# P07_DDR3_Memory.net
KiCad netlist of a schematic drawn in Altium Designer
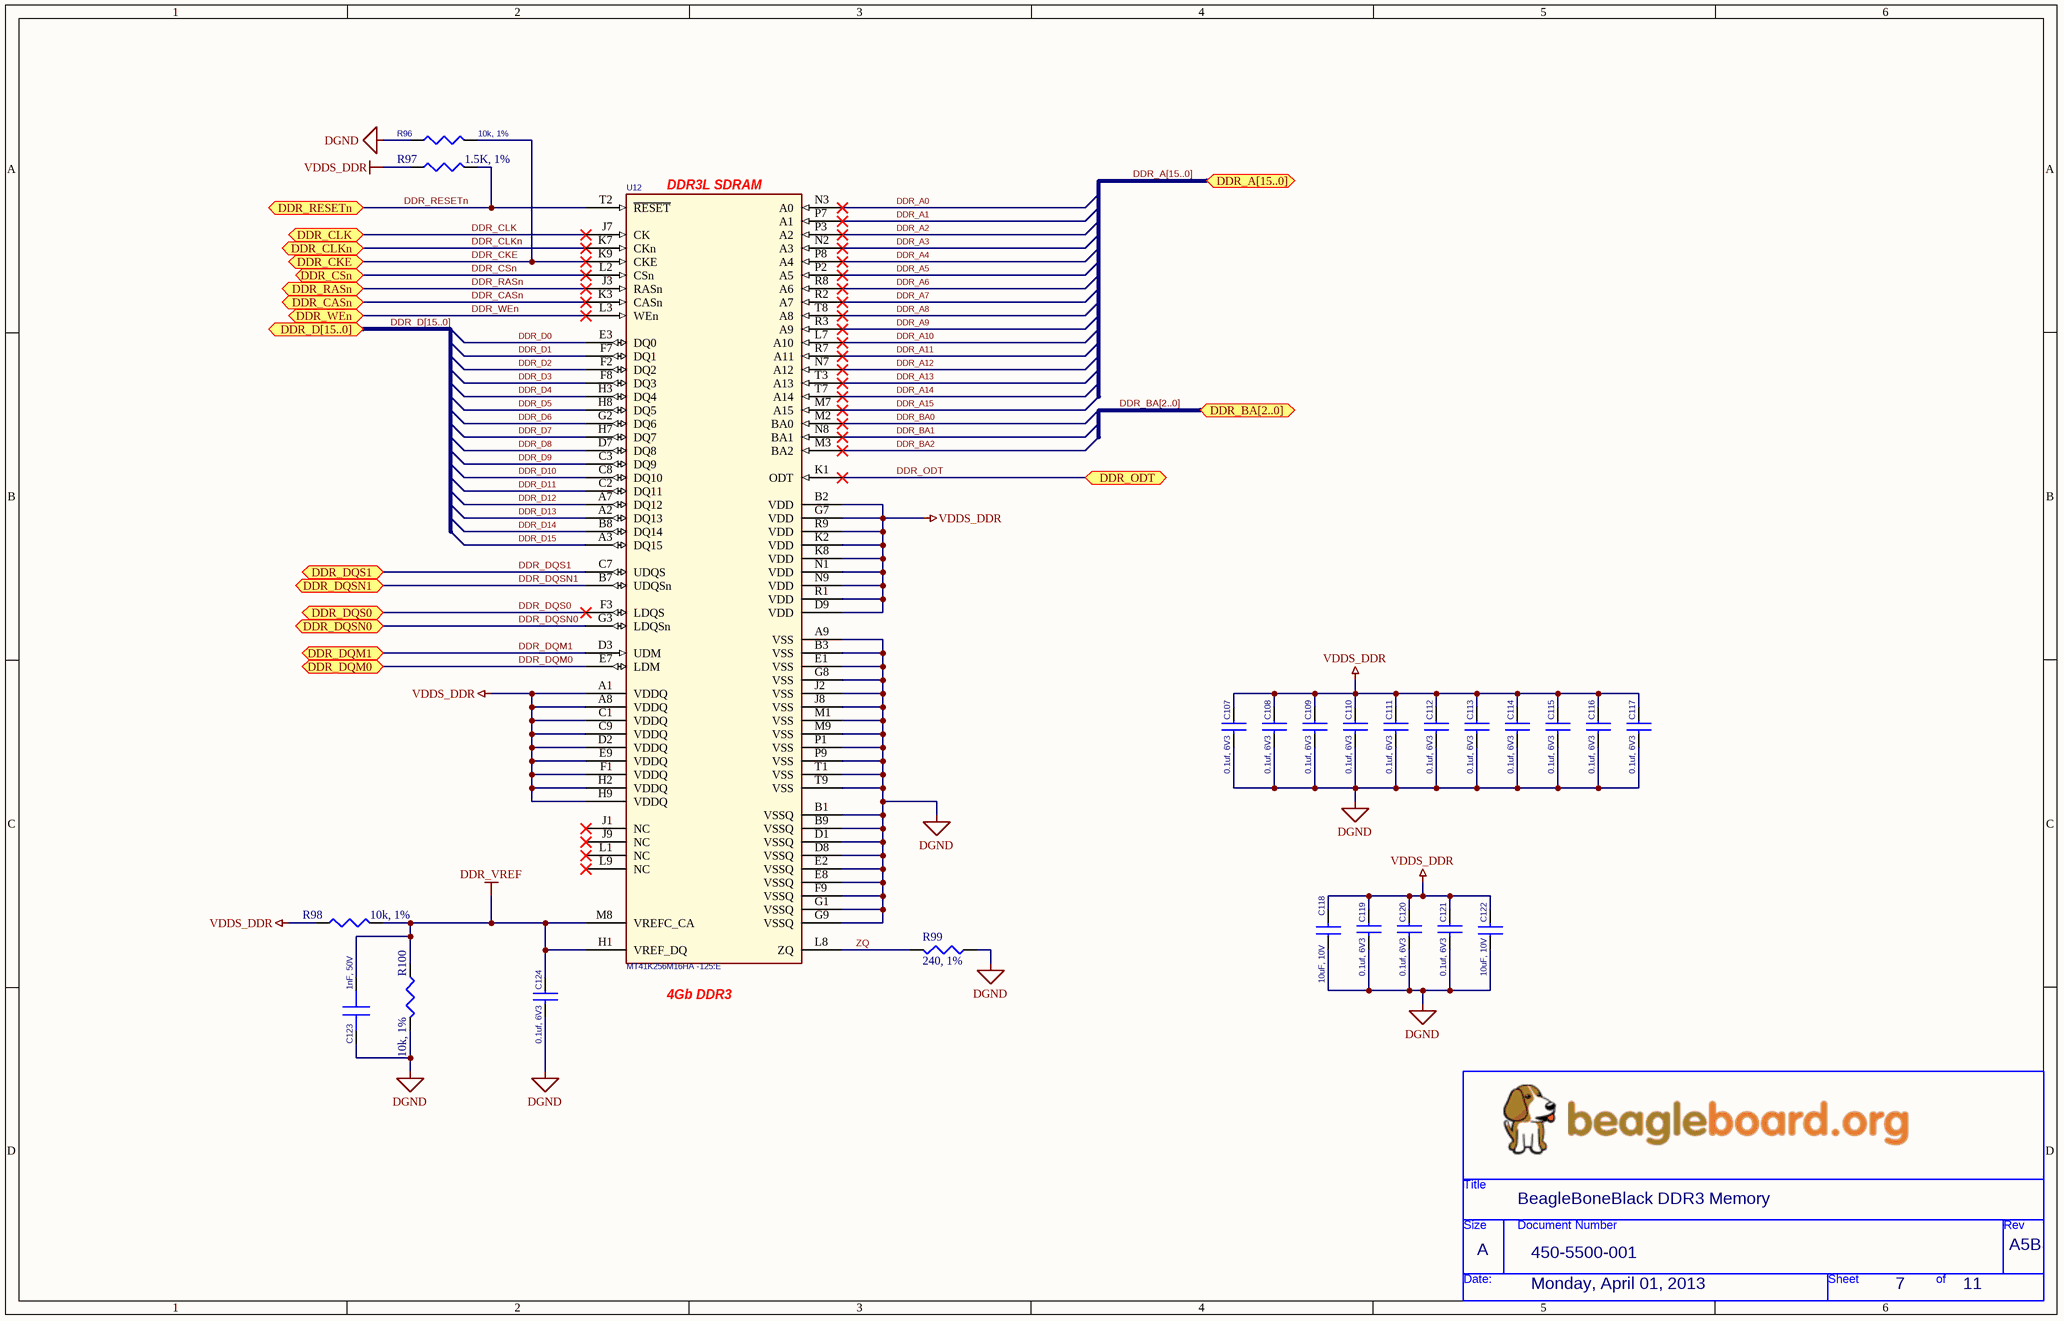
[diagram p0: P07_DDR3 Memory.SchDoc]

(export (version "E")
  (design (tool "Eeschema 10.0.6"))
  (components
    (comp (ref "C107")
      (value "0.1uf, 6V3")
      (footprint "402")
      (description "CAP CER 0.1UF 6.3V 10% X5R 0402")
      (fields
        (field (name "MANUFACTURER") "TDK Corporation")
        (field (name "MANUFACTURER PART NUMBER") "C1005X5R0J104K050BA")
      )
      (libsource (lib "BEAGLEBONEBLACK_REV A5B") (part "CAP_0.01uf_X7R_16V_10%_0402"))
    )
    (comp (ref "C108")
      (value "0.1uf, 6V3")
      (footprint "402")
      (description "CAP CER 0.1UF 6.3V 10% X5R 0402")
      (fields
        (field (name "MANUFACTURER") "TDK Corporation")
        (field (name "MANUFACTURER PART NUMBER") "C1005X5R0J104K050BA")
      )
      (libsource (lib "BEAGLEBONEBLACK_REV A5B") (part "CAP_0.01uf_X7R_16V_10%_0402"))
    )
    (comp (ref "C109")
      (value "0.1uf, 6V3")
      (footprint "402")
      (description "CAP CER 0.1UF 6.3V 10% X5R 0402")
      (fields
        (field (name "MANUFACTURER") "TDK Corporation")
        (field (name "MANUFACTURER PART NUMBER") "C1005X5R0J104K050BA")
      )
      (libsource (lib "BEAGLEBONEBLACK_REV A5B") (part "CAP_0.01uf_X7R_16V_10%_0402"))
    )
    (comp (ref "C110")
      (value "0.1uf, 6V3")
      (footprint "402")
      (description "CAP CER 0.1UF 6.3V 10% X5R 0402")
      (fields
        (field (name "MANUFACTURER") "TDK Corporation")
        (field (name "MANUFACTURER PART NUMBER") "C1005X5R0J104K050BA")
      )
      (libsource (lib "BEAGLEBONEBLACK_REV A5B") (part "CAP_0.01uf_X7R_16V_10%_0402"))
    )
    (comp (ref "C111")
      (value "0.1uf, 6V3")
      (footprint "402")
      (description "CAP CER 0.1UF 6.3V 10% X5R 0402")
      (fields
        (field (name "MANUFACTURER") "TDK Corporation")
        (field (name "MANUFACTURER PART NUMBER") "C1005X5R0J104K050BA")
      )
      (libsource (lib "BEAGLEBONEBLACK_REV A5B") (part "CAP_0.01uf_X7R_16V_10%_0402"))
    )
    (comp (ref "C112")
      (value "0.1uf, 6V3")
      (footprint "402")
      (description "CAP CER 0.1UF 6.3V 10% X5R 0402")
      (fields
        (field (name "MANUFACTURER") "TDK Corporation")
        (field (name "MANUFACTURER PART NUMBER") "C1005X5R0J104K050BA")
      )
      (libsource (lib "BEAGLEBONEBLACK_REV A5B") (part "CAP_0.01uf_X7R_16V_10%_0402"))
    )
    (comp (ref "C113")
      (value "0.1uf, 6V3")
      (footprint "402")
      (description "CAP CER 0.1UF 6.3V 10% X5R 0402")
      (fields
        (field (name "MANUFACTURER") "TDK Corporation")
        (field (name "MANUFACTURER PART NUMBER") "C1005X5R0J104K050BA")
      )
      (libsource (lib "BEAGLEBONEBLACK_REV A5B") (part "CAP_0.01uf_X7R_16V_10%_0402"))
    )
    (comp (ref "C114")
      (value "0.1uf, 6V3")
      (footprint "402")
      (description "CAP CER 0.1UF 6.3V 10% X5R 0402")
      (fields
        (field (name "MANUFACTURER") "TDK Corporation")
        (field (name "MANUFACTURER PART NUMBER") "C1005X5R0J104K050BA")
      )
      (libsource (lib "BEAGLEBONEBLACK_REV A5B") (part "CAP_0.01uf_X7R_16V_10%_0402"))
    )
    (comp (ref "C115")
      (value "0.1uf, 6V3")
      (footprint "402")
      (description "CAP CER 0.1UF 6.3V 10% X5R 0402")
      (fields
        (field (name "MANUFACTURER") "TDK Corporation")
        (field (name "MANUFACTURER PART NUMBER") "C1005X5R0J104K050BA")
      )
      (libsource (lib "BEAGLEBONEBLACK_REV A5B") (part "CAP_0.01uf_X7R_16V_10%_0402"))
    )
    (comp (ref "C116")
      (value "0.1uf, 6V3")
      (footprint "402")
      (description "CAP CER 0.1UF 6.3V 10% X5R 0402")
      (fields
        (field (name "MANUFACTURER") "TDK Corporation")
        (field (name "MANUFACTURER PART NUMBER") "C1005X5R0J104K050BA")
      )
      (libsource (lib "BEAGLEBONEBLACK_REV A5B") (part "CAP_0.01uf_X7R_16V_10%_0402"))
    )
    (comp (ref "C117")
      (value "0.1uf, 6V3")
      (footprint "402")
      (description "CAP CER 0.1UF 6.3V 10% X5R 0402")
      (fields
        (field (name "MANUFACTURER") "TDK Corporation")
        (field (name "MANUFACTURER PART NUMBER") "C1005X5R0J104K050BA")
      )
      (libsource (lib "BEAGLEBONEBLACK_REV A5B") (part "CAP_0.01uf_X7R_16V_10%_0402"))
    )
    (comp (ref "C118")
      (value "10uF, 10V")
      (footprint "805")
      (description "CAP CER 10UF 10V Y5V 0805")
      (fields
        (field (name "MANUFACTURER") "TDK Corporation")
        (field (name "MANUFACTURER PART NUMBER") "C2012Y5V1A106Z")
      )
      (libsource (lib "BEAGLEBONEBLACK_REV A5B") (part "CAP_4.7uF_X5R_6.3V_10%_0603"))
    )
    (comp (ref "C119")
      (value "0.1uf, 6V3")
      (footprint "402")
      (description "CAP CER 0.1UF 6.3V 10% X5R 0402")
      (fields
        (field (name "MANUFACTURER") "TDK Corporation")
        (field (name "MANUFACTURER PART NUMBER") "C1005X5R0J104K050BA")
      )
      (libsource (lib "BEAGLEBONEBLACK_REV A5B") (part "CAP_0.01uf_X7R_16V_10%_0402"))
    )
    (comp (ref "C120")
      (value "0.1uf, 6V3")
      (footprint "402")
      (description "CAP CER 0.1UF 6.3V 10% X5R 0402")
      (fields
        (field (name "MANUFACTURER") "TDK Corporation")
        (field (name "MANUFACTURER PART NUMBER") "C1005X5R0J104K050BA")
      )
      (libsource (lib "BEAGLEBONEBLACK_REV A5B") (part "CAP_0.01uf_X7R_16V_10%_0402"))
    )
    (comp (ref "C121")
      (value "0.1uf, 6V3")
      (footprint "402")
      (description "CAP CER 0.1UF 6.3V 10% X5R 0402")
      (fields
        (field (name "MANUFACTURER") "TDK Corporation")
        (field (name "MANUFACTURER PART NUMBER") "C1005X5R0J104K050BA")
      )
      (libsource (lib "BEAGLEBONEBLACK_REV A5B") (part "CAP_0.01uf_X7R_16V_10%_0402"))
    )
    (comp (ref "C122")
      (value "10uF, 10V")
      (footprint "805")
      (description "CAP CER 10UF 10V Y5V 0805")
      (fields
        (field (name "MANUFACTURER") "TDK Corporation")
        (field (name "MANUFACTURER PART NUMBER") "C2012Y5V1A106Z")
      )
      (libsource (lib "BEAGLEBONEBLACK_REV A5B") (part "CAP_4.7uF_X5R_6.3V_10%_0603"))
    )
    (comp (ref "C123")
      (value "1nF, 50V")
      (footprint "402")
      (description "CAP CER 1000PF 16V 10% X7R 0402")
      (fields
        (field (name "MANUFACTURER") "Yageo")
        (field (name "MANUFACTURER PART NUMBER") "CC0402KRX7R7BB102")
      )
      (libsource (lib "BEAGLEBONEBLACK_REV A5B") (part "CAP SMD"))
    )
    (comp (ref "C124")
      (value "0.1uf, 6V3")
      (footprint "402")
      (description "CAP CER 0.1UF 6.3V 10% X5R 0402")
      (fields
        (field (name "MANUFACTURER") "TDK Corporation")
        (field (name "MANUFACTURER PART NUMBER") "C1005X5R0J104K050BA")
      )
      (libsource (lib "BEAGLEBONEBLACK_REV A5B") (part "CAP_0.01uf_X7R_16V_10%_0402"))
    )
    (comp (ref "R96")
      (value "10k, 1%")
      (footprint "402")
      (description "RES 10K OHM 1/16W 5% 0402 SMD")
      (fields
        (field (name "MANUFACTURER") "Rohm Semiconductor")
        (field (name "MANUFACTURER PART NUMBER") "MCR01MZPJ103")
      )
      (libsource (lib "BEAGLEBONEBLACK_REV A5B") (part "RES_10K_1/16W_1%_0402"))
    )
    (comp (ref "R97")
      (value "1.5K, 1%")
      (footprint "402")
      (description "RES 1.50K OHM 1/16W 1% 0402 SMD")
      (fields
        (field (name "MANUFACTURER") "Yageo")
        (field (name "MANUFACTURER PART NUMBER") "RC0402FR-071K5L")
      )
      (libsource (lib "BEAGLEBONEBLACK_REV A5B") (part "RES_10K_1/16W_1%_0402"))
    )
    (comp (ref "R98")
      (value "10k, 1%")
      (footprint "402")
      (description "RES 10K OHM 1/16W 5% 0402 SMD")
      (fields
        (field (name "MANUFACTURER") "Rohm Semiconductor")
        (field (name "MANUFACTURER PART NUMBER") "MCR01MZPJ103")
      )
      (libsource (lib "BEAGLEBONEBLACK_REV A5B") (part "RES_10K_1/16W_1%_0402"))
    )
    (comp (ref "R99")
      (value "240, 1%")
      (footprint "402")
      (description "RES 240 OHM 1/10W 5% 0402 SMD")
      (fields
        (field (name "MANUFACTURER") "Yageo")
        (field (name "MANUFACTURER PART NUMBER") "RC0402FR-07240RL")
      )
      (libsource (lib "BEAGLEBONEBLACK_REV A5B") (part "RES_10K_1/16W_1%_0402"))
    )
    (comp (ref "R100")
      (value "10k, 1%")
      (footprint "402")
      (description "RES 10K OHM 1/16W 5% 0402 SMD")
      (fields
        (field (name "MANUFACTURER") "Rohm Semiconductor")
        (field (name "MANUFACTURER PART NUMBER") "MCR01MZPJ103")
      )
      (libsource (lib "BEAGLEBONEBLACK_REV A5B") (part "RES_10K_1/16W_1%_0402"))
    )
    (comp (ref "U12")
      (value "MT41K256M16HA -125:E")
      (footprint "BGA96_T9_P8_9X14")
      (description "DDR2 SDRAM 2Gb (256Mx8)")
      (fields
        (field (name "MANUFACTURER") "Micron Technology")
        (field (name "MANUFACTURER PART NUMBER") "MT41K256M16HA-125:E")
      )
      (libsource (lib "BEAGLEBONEBLACK_REV A5B") (part "MT41K256M16HA"))
    )
  )
  (nets
    (net (code "1") (name "/DDR_A0") (class "Default")
      (node (ref "U12") (pin "N3") (pinfunction "A0_N3") (pintype "input+no_connect"))
    )
    (net (code "2") (name "/DDR_A1") (class "Default")
      (node (ref "U12") (pin "P7") (pinfunction "A1_P7") (pintype "input+no_connect"))
    )
    (net (code "3") (name "/DDR_A2") (class "Default")
      (node (ref "U12") (pin "P3") (pinfunction "A2_P3") (pintype "input+no_connect"))
    )
    (net (code "4") (name "/DDR_A3") (class "Default")
      (node (ref "U12") (pin "N2") (pinfunction "A3_N2") (pintype "input+no_connect"))
    )
    (net (code "5") (name "/DDR_A4") (class "Default")
      (node (ref "U12") (pin "P8") (pinfunction "A4_P8") (pintype "input+no_connect"))
    )
    (net (code "6") (name "/DDR_A5") (class "Default")
      (node (ref "U12") (pin "P2") (pinfunction "A5_P2") (pintype "input+no_connect"))
    )
    (net (code "7") (name "/DDR_A6") (class "Default")
      (node (ref "U12") (pin "R8") (pinfunction "A6_R8") (pintype "input+no_connect"))
    )
    (net (code "8") (name "/DDR_A7") (class "Default")
      (node (ref "U12") (pin "R2") (pinfunction "A7_R2") (pintype "input+no_connect"))
    )
    (net (code "9") (name "/DDR_A8") (class "Default")
      (node (ref "U12") (pin "T8") (pinfunction "A8_T8") (pintype "input+no_connect"))
    )
    (net (code "10") (name "/DDR_A9") (class "Default")
      (node (ref "U12") (pin "R3") (pinfunction "A9_R3") (pintype "input+no_connect"))
    )
    (net (code "11") (name "/DDR_A10") (class "Default")
      (node (ref "U12") (pin "L7") (pinfunction "A10_L7") (pintype "input+no_connect"))
    )
    (net (code "12") (name "/DDR_A11") (class "Default")
      (node (ref "U12") (pin "R7") (pinfunction "A11_R7") (pintype "input+no_connect"))
    )
    (net (code "13") (name "/DDR_A12") (class "Default")
      (node (ref "U12") (pin "N7") (pinfunction "A12_N7") (pintype "input+no_connect"))
    )
    (net (code "14") (name "/DDR_A13") (class "Default")
      (node (ref "U12") (pin "T3") (pinfunction "A13_T3") (pintype "input+no_connect"))
    )
    (net (code "15") (name "/DDR_A14") (class "Default")
      (node (ref "U12") (pin "T7") (pinfunction "A14_T7") (pintype "input+no_connect"))
    )
    (net (code "16") (name "/DDR_A15") (class "Default")
      (node (ref "U12") (pin "M7") (pinfunction "A15_M7") (pintype "input+no_connect"))
    )
    (net (code "18") (name "/DDR_BA0") (class "Default")
      (node (ref "U12") (pin "M2") (pinfunction "BA0_M2") (pintype "input+no_connect"))
    )
    (net (code "19") (name "/DDR_BA1") (class "Default")
      (node (ref "U12") (pin "N8") (pinfunction "BA1_N8") (pintype "input+no_connect"))
    )
    (net (code "20") (name "/DDR_BA2") (class "Default")
      (node (ref "U12") (pin "M3") (pinfunction "BA2_M3") (pintype "input+no_connect"))
    )
    (net (code "22") (name "/DDR_CASn") (class "Default")
      (node (ref "U12") (pin "K3") (pinfunction "CASn_K3") (pintype "input+no_connect"))
    )
    (net (code "23") (name "/DDR_CKE") (class "Default")
      (node (ref "R96") (pin "2") (pinfunction "2_2") (pintype "passive"))
      (node (ref "U12") (pin "K9") (pinfunction "CKE_K9") (pintype "input"))
    )
    (net (code "24") (name "/DDR_CLK") (class "Default")
      (node (ref "U12") (pin "J7") (pinfunction "CK_J7") (pintype "input+no_connect"))
    )
    (net (code "25") (name "/DDR_CLKn") (class "Default")
      (node (ref "U12") (pin "K7") (pinfunction "CKn_K7") (pintype "input+no_connect"))
    )
    (net (code "26") (name "/DDR_CSn") (class "Default")
      (node (ref "U12") (pin "L2") (pinfunction "CSn_L2") (pintype "input+no_connect"))
    )
    (net (code "27") (name "/DDR_D0") (class "Default")
      (node (ref "U12") (pin "E3") (pinfunction "DQ0_E3") (pintype "bidirectional"))
    )
    (net (code "28") (name "/DDR_D1") (class "Default")
      (node (ref "U12") (pin "F7") (pinfunction "DQ1_F7") (pintype "bidirectional"))
    )
    (net (code "29") (name "/DDR_D2") (class "Default")
      (node (ref "U12") (pin "F2") (pinfunction "DQ2_F2") (pintype "bidirectional"))
    )
    (net (code "30") (name "/DDR_D3") (class "Default")
      (node (ref "U12") (pin "F8") (pinfunction "DQ3_F8") (pintype "bidirectional"))
    )
    (net (code "31") (name "/DDR_D4") (class "Default")
      (node (ref "U12") (pin "H3") (pinfunction "DQ4_H3") (pintype "bidirectional"))
    )
    (net (code "32") (name "/DDR_D5") (class "Default")
      (node (ref "U12") (pin "H8") (pinfunction "DQ5_H8") (pintype "bidirectional"))
    )
    (net (code "33") (name "/DDR_D6") (class "Default")
      (node (ref "U12") (pin "G2") (pinfunction "DQ6_G2") (pintype "bidirectional"))
    )
    (net (code "34") (name "/DDR_D7") (class "Default")
      (node (ref "U12") (pin "H7") (pinfunction "DQ7_H7") (pintype "bidirectional"))
    )
    (net (code "35") (name "/DDR_D8") (class "Default")
      (node (ref "U12") (pin "D7") (pinfunction "DQ8_D7") (pintype "bidirectional"))
    )
    (net (code "36") (name "/DDR_D9") (class "Default")
      (node (ref "U12") (pin "C3") (pinfunction "DQ9_C3") (pintype "bidirectional"))
    )
    (net (code "37") (name "/DDR_D10") (class "Default")
      (node (ref "U12") (pin "C8") (pinfunction "DQ10_C8") (pintype "bidirectional"))
    )
    (net (code "38") (name "/DDR_D11") (class "Default")
      (node (ref "U12") (pin "C2") (pinfunction "DQ11_C2") (pintype "bidirectional"))
    )
    (net (code "39") (name "/DDR_D12") (class "Default")
      (node (ref "U12") (pin "A7") (pinfunction "DQ12_A7") (pintype "bidirectional"))
    )
    (net (code "40") (name "/DDR_D13") (class "Default")
      (node (ref "U12") (pin "A2") (pinfunction "DQ13_A2") (pintype "bidirectional"))
    )
    (net (code "41") (name "/DDR_D14") (class "Default")
      (node (ref "U12") (pin "B8") (pinfunction "DQ14_B8") (pintype "bidirectional"))
    )
    (net (code "42") (name "/DDR_D15") (class "Default")
      (node (ref "U12") (pin "A3") (pinfunction "DQ15_A3") (pintype "bidirectional"))
    )
    (net (code "43") (name "/DDR_DQM0") (class "Default")
      (node (ref "U12") (pin "E7") (pinfunction "LDM_E7") (pintype "bidirectional"))
    )
    (net (code "44") (name "/DDR_DQM1") (class "Default")
      (node (ref "U12") (pin "D3") (pinfunction "UDM_D3") (pintype "input"))
    )
    (net (code "45") (name "/DDR_DQS0") (class "Default")
      (node (ref "U12") (pin "F3") (pinfunction "LDQS_F3") (pintype "bidirectional+no_connect"))
    )
    (net (code "46") (name "/DDR_DQS1") (class "Default")
      (node (ref "U12") (pin "C7") (pinfunction "UDQS_C7") (pintype "bidirectional"))
    )
    (net (code "47") (name "/DDR_DQSN0") (class "Default")
      (node (ref "U12") (pin "G3") (pinfunction "LDQSn_G3") (pintype "bidirectional"))
    )
    (net (code "48") (name "/DDR_DQSN1") (class "Default")
      (node (ref "U12") (pin "B7") (pinfunction "UDQSn_B7") (pintype "bidirectional"))
    )
    (net (code "50") (name "/DDR_ODT") (class "Default")
      (node (ref "U12") (pin "K1") (pinfunction "ODT_K1") (pintype "input+no_connect"))
    )
    (net (code "51") (name "/DDR_RASn") (class "Default")
      (node (ref "U12") (pin "J3") (pinfunction "RASn_J3") (pintype "input+no_connect"))
    )
    (net (code "52") (name "/DDR_RESETn") (class "Default")
      (node (ref "R97") (pin "2") (pinfunction "2_2") (pintype "passive"))
      (node (ref "U12") (pin "T2") (pinfunction "~{RESET}_T2") (pintype "input"))
    )
    (net (code "53") (name "/DDR_WEn") (class "Default")
      (node (ref "U12") (pin "L3") (pinfunction "WEn_L3") (pintype "input+no_connect"))
    )
    (net (code "54") (name "/ZQ") (class "Default")
      (node (ref "R99") (pin "2") (pinfunction "2_2") (pintype "passive"))
      (node (ref "U12") (pin "L8") (pinfunction "ZQ_L8") (pintype "passive"))
    )
    (net (code "55") (name "DDR_VREF") (class "Default")
      (node (ref "C123") (pin "1") (pinfunction "1_1") (pintype "passive"))
      (node (ref "C124") (pin "1") (pinfunction "1_1") (pintype "passive"))
      (node (ref "R100") (pin "1") (pinfunction "1_1") (pintype "passive"))
      (node (ref "R98") (pin "2") (pinfunction "2_2") (pintype "passive"))
      (node (ref "U12") (pin "H1") (pinfunction "VREF_DQ_H1") (pintype "passive"))
      (node (ref "U12") (pin "M8") (pinfunction "VREFC_CA_M8") (pintype "power_in"))
    )
    (net (code "56") (name "DGND") (class "Default")
      (node (ref "C107") (pin "2") (pinfunction "2_2") (pintype "passive"))
      (node (ref "C108") (pin "2") (pinfunction "2_2") (pintype "passive"))
      (node (ref "C109") (pin "2") (pinfunction "2_2") (pintype "passive"))
      (node (ref "C110") (pin "2") (pinfunction "2_2") (pintype "passive"))
      (node (ref "C111") (pin "2") (pinfunction "2_2") (pintype "passive"))
      (node (ref "C112") (pin "2") (pinfunction "2_2") (pintype "passive"))
      (node (ref "C113") (pin "2") (pinfunction "2_2") (pintype "passive"))
      (node (ref "C114") (pin "2") (pinfunction "2_2") (pintype "passive"))
      (node (ref "C115") (pin "2") (pinfunction "2_2") (pintype "passive"))
      (node (ref "C116") (pin "2") (pinfunction "2_2") (pintype "passive"))
      (node (ref "C117") (pin "2") (pinfunction "2_2") (pintype "passive"))
      (node (ref "C118") (pin "1") (pinfunction "1_1") (pintype "passive"))
      (node (ref "C119") (pin "2") (pinfunction "2_2") (pintype "passive"))
      (node (ref "C120") (pin "2") (pinfunction "2_2") (pintype "passive"))
      (node (ref "C121") (pin "2") (pinfunction "2_2") (pintype "passive"))
      (node (ref "C122") (pin "1") (pinfunction "1_1") (pintype "passive"))
      (node (ref "C123") (pin "2") (pinfunction "2_2") (pintype "passive"))
      (node (ref "C124") (pin "2") (pinfunction "2_2") (pintype "passive"))
      (node (ref "R100") (pin "2") (pinfunction "2_2") (pintype "passive"))
      (node (ref "R96") (pin "1") (pinfunction "1_1") (pintype "passive"))
      (node (ref "R99") (pin "1") (pinfunction "1_1") (pintype "passive"))
      (node (ref "U12") (pin "A9") (pinfunction "VSS_A9") (pintype "power_in"))
      (node (ref "U12") (pin "B1") (pinfunction "VSSQ_B1") (pintype "power_in"))
      (node (ref "U12") (pin "B3") (pinfunction "VSS_B3") (pintype "power_in"))
      (node (ref "U12") (pin "B9") (pinfunction "VSSQ_B9") (pintype "power_in"))
      (node (ref "U12") (pin "D1") (pinfunction "VSSQ_D1") (pintype "power_in"))
      (node (ref "U12") (pin "D8") (pinfunction "VSSQ_D8") (pintype "power_in"))
      (node (ref "U12") (pin "E1") (pinfunction "VSS_E1") (pintype "power_in"))
      (node (ref "U12") (pin "E2") (pinfunction "VSSQ_E2") (pintype "power_in"))
      (node (ref "U12") (pin "E8") (pinfunction "VSSQ_E8") (pintype "power_in"))
      (node (ref "U12") (pin "F9") (pinfunction "VSSQ_F9") (pintype "power_in"))
      (node (ref "U12") (pin "G1") (pinfunction "VSSQ_G1") (pintype "power_in"))
      (node (ref "U12") (pin "G8") (pinfunction "VSS_G8") (pintype "power_in"))
      (node (ref "U12") (pin "G9") (pinfunction "VSSQ_G9") (pintype "power_in"))
      (node (ref "U12") (pin "J2") (pinfunction "VSS_J2") (pintype "power_in"))
      (node (ref "U12") (pin "J8") (pinfunction "VSS_J8") (pintype "power_in"))
      (node (ref "U12") (pin "M1") (pinfunction "VSS_M1") (pintype "power_in"))
      (node (ref "U12") (pin "M9") (pinfunction "VSS_M9") (pintype "power_in"))
      (node (ref "U12") (pin "P1") (pinfunction "VSS_P1") (pintype "power_in"))
      (node (ref "U12") (pin "P9") (pinfunction "VSS_P9") (pintype "power_in"))
      (node (ref "U12") (pin "T1") (pinfunction "VSS_T1") (pintype "power_in"))
      (node (ref "U12") (pin "T9") (pinfunction "VSS_T9") (pintype "power_in"))
    )
    (net (code "57") (name "VDDS_DDR") (class "Default")
      (node (ref "C107") (pin "1") (pinfunction "1_1") (pintype "passive"))
      (node (ref "C108") (pin "1") (pinfunction "1_1") (pintype "passive"))
      (node (ref "C109") (pin "1") (pinfunction "1_1") (pintype "passive"))
      (node (ref "C110") (pin "1") (pinfunction "1_1") (pintype "passive"))
      (node (ref "C111") (pin "1") (pinfunction "1_1") (pintype "passive"))
      (node (ref "C112") (pin "1") (pinfunction "1_1") (pintype "passive"))
      (node (ref "C113") (pin "1") (pinfunction "1_1") (pintype "passive"))
      (node (ref "C114") (pin "1") (pinfunction "1_1") (pintype "passive"))
      (node (ref "C115") (pin "1") (pinfunction "1_1") (pintype "passive"))
      (node (ref "C116") (pin "1") (pinfunction "1_1") (pintype "passive"))
      (node (ref "C117") (pin "1") (pinfunction "1_1") (pintype "passive"))
      (node (ref "C118") (pin "2") (pinfunction "2_2") (pintype "passive"))
      (node (ref "C119") (pin "1") (pinfunction "1_1") (pintype "passive"))
      (node (ref "C120") (pin "1") (pinfunction "1_1") (pintype "passive"))
      (node (ref "C121") (pin "1") (pinfunction "1_1") (pintype "passive"))
      (node (ref "C122") (pin "2") (pinfunction "2_2") (pintype "passive"))
      (node (ref "R97") (pin "1") (pinfunction "1_1") (pintype "passive"))
      (node (ref "R98") (pin "1") (pinfunction "1_1") (pintype "passive"))
      (node (ref "U12") (pin "A1") (pinfunction "VDDQ_A1") (pintype "power_in"))
      (node (ref "U12") (pin "A8") (pinfunction "VDDQ_A8") (pintype "power_in"))
      (node (ref "U12") (pin "B2") (pinfunction "VDD_B2") (pintype "power_in"))
      (node (ref "U12") (pin "C1") (pinfunction "VDDQ_C1") (pintype "power_in"))
      (node (ref "U12") (pin "C9") (pinfunction "VDDQ_C9") (pintype "power_in"))
      (node (ref "U12") (pin "D2") (pinfunction "VDDQ_D2") (pintype "power_in"))
      (node (ref "U12") (pin "D9") (pinfunction "VDD_D9") (pintype "power_in"))
      (node (ref "U12") (pin "E9") (pinfunction "VDDQ_E9") (pintype "power_in"))
      (node (ref "U12") (pin "F1") (pinfunction "VDDQ_F1") (pintype "power_in"))
      (node (ref "U12") (pin "G7") (pinfunction "VDD_G7") (pintype "power_in"))
      (node (ref "U12") (pin "H2") (pinfunction "VDDQ_H2") (pintype "power_in"))
      (node (ref "U12") (pin "H9") (pinfunction "VDDQ_H9") (pintype "power_in"))
      (node (ref "U12") (pin "K2") (pinfunction "VDD_K2") (pintype "power_in"))
      (node (ref "U12") (pin "K8") (pinfunction "VDD_K8") (pintype "power_in"))
      (node (ref "U12") (pin "N1") (pinfunction "VDD_N1") (pintype "power_in"))
      (node (ref "U12") (pin "N9") (pinfunction "VDD_N9") (pintype "power_in"))
      (node (ref "U12") (pin "R1") (pinfunction "VDD_R1") (pintype "power_in"))
      (node (ref "U12") (pin "R9") (pinfunction "VDD_R9") (pintype "power_in"))
    )
    (net (code "58") (name "unconnected-(U12-NC-PadJ1)") (class "Default")
      (node (ref "U12") (pin "J1") (pinfunction "NC_J1") (pintype "passive+no_connect"))
    )
    (net (code "59") (name "unconnected-(U12-NC-PadJ9)") (class "Default")
      (node (ref "U12") (pin "J9") (pinfunction "NC_J9") (pintype "passive+no_connect"))
    )
    (net (code "60") (name "unconnected-(U12-NC-PadL1)") (class "Default")
      (node (ref "U12") (pin "L1") (pinfunction "NC_L1") (pintype "power_in+no_connect"))
    )
    (net (code "61") (name "unconnected-(U12-NC-PadL9)") (class "Default")
      (node (ref "U12") (pin "L9") (pinfunction "NC_L9") (pintype "power_in+no_connect"))
    )
  )
)
